# UDEMY_Sheet.net
KiCad netlist of a schematic drawn in Altium Designer
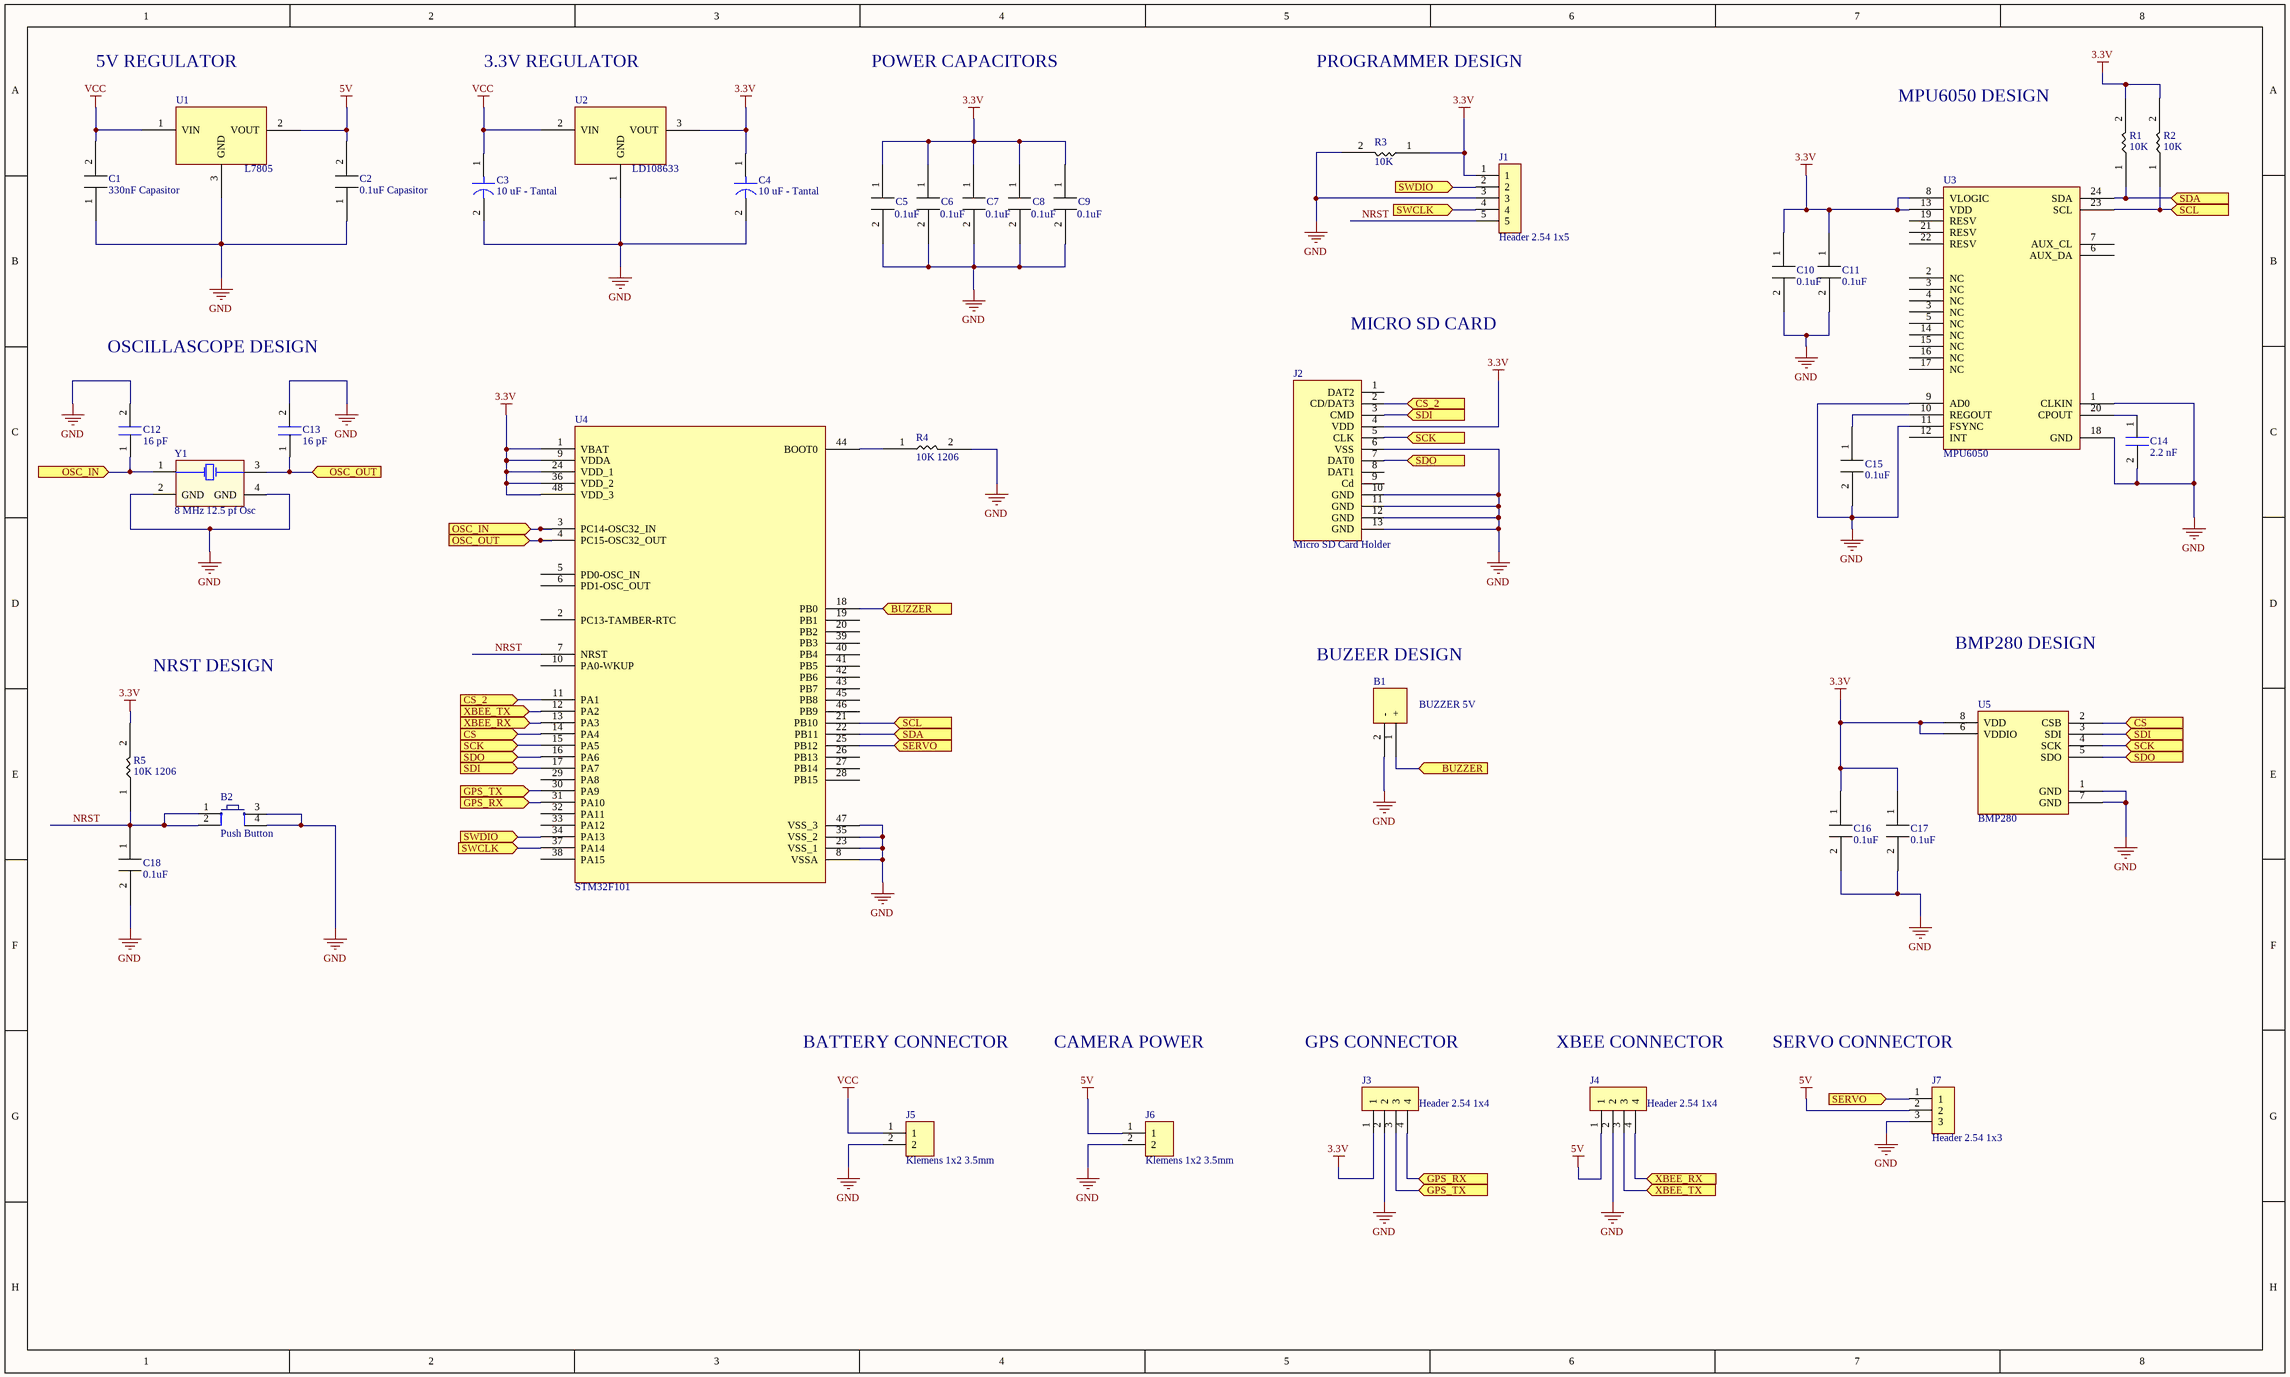
[diagram p0: UDEMY_Sheet.SchDoc]

(export (version "E")
  (design (tool "Eeschema 10.0.6"))
  (components
    (comp (ref "B1")
      (value "BUZZER 5V")
      (footprint "BUZZER 5V")
      (libsource (lib "UDEMY_Schlib1SchLib") (part "BUZZER 5V"))
    )
    (comp (ref "B2")
      (value "Push Button")
      (footprint "PUSB BUTTON-SMD")
      (description "Smd Push Button")
      (libsource (lib "UDEMY_Schlib1SchLib") (part "Push Button"))
    )
    (comp (ref "C1")
      (value "330nF Capasitor")
      (footprint "CAP 1206")
      (libsource (lib "UDEMY_Schlib1SchLib") (part "330nF Capasitor"))
    )
    (comp (ref "C2")
      (value "0.1uF Capasitor")
      (footprint "CAP 1206")
      (libsource (lib "UDEMY_Schlib1SchLib") (part "0.1uF Capasitor"))
    )
    (comp (ref "C3")
      (value "10 uF - Tantal")
      (footprint "C1206- TANTAL")
      (libsource (lib "UDEMY_Schlib1SchLib") (part "10 uF - Tantal"))
    )
    (comp (ref "C4")
      (value "10 uF - Tantal")
      (footprint "C1206- TANTAL")
      (libsource (lib "UDEMY_Schlib1SchLib") (part "10 uF - Tantal"))
    )
    (comp (ref "C5")
      (value "0.1uF")
      (footprint "CAP 1206")
      (description "0.1uF Capasitor")
      (libsource (lib "UDEMY_Schlib1SchLib") (part "0.1uF Capasitor"))
    )
    (comp (ref "C6")
      (value "0.1uF")
      (footprint "CAP 1206")
      (description "0.1uF Capasitor")
      (libsource (lib "UDEMY_Schlib1SchLib") (part "0.1uF Capasitor"))
    )
    (comp (ref "C7")
      (value "0.1uF")
      (footprint "CAP 1206")
      (description "0.1uF Capasitor")
      (libsource (lib "UDEMY_Schlib1SchLib") (part "0.1uF Capasitor"))
    )
    (comp (ref "C8")
      (value "0.1uF")
      (footprint "CAP 1206")
      (description "0.1uF Capasitor")
      (libsource (lib "UDEMY_Schlib1SchLib") (part "0.1uF Capasitor"))
    )
    (comp (ref "C9")
      (value "0.1uF")
      (footprint "CAP 1206")
      (description "0.1uF Capasitor")
      (libsource (lib "UDEMY_Schlib1SchLib") (part "0.1uF Capasitor"))
    )
    (comp (ref "C10")
      (value "0.1uF")
      (footprint "CAP 1206")
      (description "0.1uF Capasitor")
      (libsource (lib "UDEMY_Schlib1SchLib") (part "0.1uF Capasitor"))
    )
    (comp (ref "C11")
      (value "0.1uF")
      (footprint "CAP 1206")
      (description "0.1uF Capasitor")
      (libsource (lib "UDEMY_Schlib1SchLib") (part "0.1uF Capasitor"))
    )
    (comp (ref "C12")
      (value "16 pF")
      (footprint "CAP 1206")
      (libsource (lib "UDEMY_Schlib1SchLib") (part "16 pF"))
    )
    (comp (ref "C13")
      (value "16 pF")
      (footprint "CAP 1206")
      (libsource (lib "UDEMY_Schlib1SchLib") (part "16 pF"))
    )
    (comp (ref "C14")
      (value "2.2 nF")
      (footprint "CAP 1206")
      (description "2.2 nF c1206")
      (libsource (lib "UDEMY_Schlib1SchLib") (part "2.2 nF c1206"))
    )
    (comp (ref "C15")
      (value "0.1uF")
      (footprint "CAP 1206")
      (description "0.1uF Capasitor")
      (libsource (lib "UDEMY_Schlib1SchLib") (part "0.1uF Capasitor"))
    )
    (comp (ref "C16")
      (value "0.1uF")
      (footprint "CAP 1206")
      (description "0.1uF Capasitor")
      (libsource (lib "UDEMY_Schlib1SchLib") (part "0.1uF Capasitor"))
    )
    (comp (ref "C17")
      (value "0.1uF")
      (footprint "CAP 1206")
      (description "0.1uF Capasitor")
      (libsource (lib "UDEMY_Schlib1SchLib") (part "0.1uF Capasitor"))
    )
    (comp (ref "C18")
      (value "0.1uF")
      (footprint "CAP 1206")
      (description "0.1uF Capasitor")
      (libsource (lib "UDEMY_Schlib1SchLib") (part "0.1uF Capasitor"))
    )
    (comp (ref "J1")
      (value "Header 2.54 1x5")
      (footprint "Header 2.54 1x5")
      (libsource (lib "UDEMY_Schlib1SchLib") (part "Header 2.54 1x5"))
    )
    (comp (ref "J2")
      (value "Micro SD Card Holder")
      (footprint "Micro SD Card Holder")
      (libsource (lib "UDEMY_Schlib1SchLib") (part "Micro SD Card Holder"))
    )
    (comp (ref "J3")
      (value "Header 2.54 1x4")
      (footprint "Header 2.54 1x4")
      (libsource (lib "UDEMY_Schlib1SchLib") (part "Header 2.54 1x4"))
    )
    (comp (ref "J4")
      (value "Header 2.54 1x4")
      (footprint "Header 2.54 1x4")
      (libsource (lib "UDEMY_Schlib1SchLib") (part "Header 2.54 1x4"))
    )
    (comp (ref "J5")
      (value "Klemens 1x2 3.5mm")
      (footprint "Klemens 1x2 - 3.5mm")
      (libsource (lib "UDEMY_Schlib1SchLib") (part "Klemens 1x2 3.5mm"))
    )
    (comp (ref "J6")
      (value "Klemens 1x2 3.5mm")
      (footprint "Klemens 1x2 - 3.5mm")
      (libsource (lib "UDEMY_Schlib1SchLib") (part "Klemens 1x2 3.5mm"))
    )
    (comp (ref "J7")
      (value "Header 2.54 1x3")
      (footprint "Header 2.54 1x3")
      (libsource (lib "UDEMY_Schlib1SchLib") (part "Header 2.54 1x3"))
    )
    (comp (ref "R1")
      (value "10K")
      (footprint "1206 RES")
      (description "10K 1206")
      (libsource (lib "UDEMY_Schlib1SchLib") (part "10K 1206"))
    )
    (comp (ref "R2")
      (value "10K")
      (footprint "1206 RES")
      (description "10K 1206")
      (libsource (lib "UDEMY_Schlib1SchLib") (part "10K 1206"))
    )
    (comp (ref "R3")
      (value "10K")
      (footprint "1206 RES")
      (description "10K 1206")
      (libsource (lib "UDEMY_Schlib1SchLib") (part "10K 1206"))
    )
    (comp (ref "R4")
      (value "10K 1206")
      (footprint "1206 RES")
      (libsource (lib "UDEMY_Schlib1SchLib") (part "10K 1206"))
    )
    (comp (ref "R5")
      (value "10K 1206")
      (footprint "1206 RES")
      (libsource (lib "UDEMY_Schlib1SchLib") (part "10K 1206"))
    )
    (comp (ref "U1")
      (value "L7805")
      (footprint "DPAK228P972X230-3N")
      (description "L7805 5V REGULATOR DPAK")
      (libsource (lib "UDEMY_Schlib1SchLib") (part "L7805"))
    )
    (comp (ref "U2")
      (value "LD108633")
      (footprint "DPAK228P972X230-3N")
      (description "LD108633 3.3V REGULATOR DPAK")
      (libsource (lib "UDEMY_Schlib1SchLib") (part "LD108633"))
    )
    (comp (ref "U3")
      (value "MPU6050")
      (footprint "QFN50P400X400X90_HS-25N")
      (description "MPU6050 GYRO")
      (libsource (lib "UDEMY_Schlib1SchLib") (part "MPU6050"))
    )
    (comp (ref "U4")
      (value "STM32F101")
      (footprint "LQFP48-STM")
      (description "STM32F101 48 pinli mikrodenetleyicisi")
      (libsource (lib "UDEMY_Schlib1SchLib") (part "STM32F101"))
    )
    (comp (ref "U5")
      (value "BMP280")
      (footprint "BMP280")
      (description "BMP280 SENSOR")
      (libsource (lib "UDEMY_Schlib1SchLib") (part "BMP280"))
    )
    (comp (ref "Y1")
      (value "8 MHz 12.5 pf Osc")
      (footprint "8 MHZ Osc.")
      (libsource (lib "UDEMY_Schlib1SchLib") (part "8 MHz 12.5 pf Osc"))
    )
  )
  (nets
    (net (code "1") (name "/BUZZER") (class "Default")
      (node (ref "B1") (pin "1") (pinfunction "+_1") (pintype "passive"))
      (node (ref "U4") (pin "18") (pinfunction "PB0_18") (pintype "passive"))
    )
    (net (code "2") (name "/CS") (class "Default")
      (node (ref "U4") (pin "14") (pinfunction "PA4_14") (pintype "passive"))
      (node (ref "U5") (pin "2") (pinfunction "CSB_2") (pintype "passive"))
    )
    (net (code "3") (name "/CS_2") (class "Default")
      (node (ref "J2") (pin "2") (pinfunction "CD/DAT3_2") (pintype "passive"))
      (node (ref "U4") (pin "11") (pinfunction "PA1_11") (pintype "passive"))
    )
    (net (code "4") (name "/GPS_RX") (class "Default")
      (node (ref "J3") (pin "4") (pinfunction "4_4") (pintype "passive"))
      (node (ref "U4") (pin "31") (pinfunction "PA10_31") (pintype "passive"))
    )
    (net (code "5") (name "/GPS_TX") (class "Default")
      (node (ref "J3") (pin "3") (pinfunction "3_3") (pintype "passive"))
      (node (ref "U4") (pin "30") (pinfunction "PA9_30") (pintype "passive"))
    )
    (net (code "6") (name "/NRST") (class "Default")
      (node (ref "B2") (pin "1") (pinfunction "1_1") (pintype "passive"))
      (node (ref "B2") (pin "2") (pinfunction "2_2") (pintype "passive"))
      (node (ref "C18") (pin "1") (pinfunction "1_1") (pintype "passive"))
      (node (ref "J1") (pin "5") (pinfunction "5_5") (pintype "passive"))
      (node (ref "R5") (pin "1") (pinfunction "1_1") (pintype "passive"))
      (node (ref "U4") (pin "7") (pinfunction "NRST_7") (pintype "passive"))
    )
    (net (code "7") (name "/OSC_IN") (class "Default")
      (node (ref "C12") (pin "1") (pinfunction "1_1") (pintype "passive"))
      (node (ref "U4") (pin "3") (pinfunction "PC14-OSC32_IN_3") (pintype "passive"))
      (node (ref "Y1") (pin "1") (pintype "power_in"))
    )
    (net (code "8") (name "/OSC_OUT") (class "Default")
      (node (ref "C13") (pin "1") (pinfunction "1_1") (pintype "passive"))
      (node (ref "U4") (pin "4") (pinfunction "PC15-OSC32_OUT_4") (pintype "passive"))
      (node (ref "Y1") (pin "3") (pintype "passive"))
    )
    (net (code "9") (name "/SCK") (class "Default")
      (node (ref "J2") (pin "5") (pinfunction "CLK_5") (pintype "passive"))
      (node (ref "U4") (pin "15") (pinfunction "PA5_15") (pintype "passive"))
      (node (ref "U5") (pin "4") (pinfunction "SCK_4") (pintype "passive"))
    )
    (net (code "10") (name "/SCL") (class "Default")
      (node (ref "R2") (pin "1") (pinfunction "1_1") (pintype "passive"))
      (node (ref "U3") (pin "23") (pinfunction "SCL_23") (pintype "passive"))
      (node (ref "U4") (pin "21") (pinfunction "PB10_21") (pintype "passive"))
    )
    (net (code "11") (name "/SDA") (class "Default")
      (node (ref "R1") (pin "1") (pinfunction "1_1") (pintype "passive"))
      (node (ref "U3") (pin "24") (pinfunction "SDA_24") (pintype "passive"))
      (node (ref "U4") (pin "22") (pinfunction "PB11_22") (pintype "passive"))
    )
    (net (code "12") (name "/SDI") (class "Default")
      (node (ref "J2") (pin "3") (pinfunction "CMD_3") (pintype "passive"))
      (node (ref "U4") (pin "17") (pinfunction "PA7_17") (pintype "passive"))
      (node (ref "U5") (pin "3") (pinfunction "SDI_3") (pintype "passive"))
    )
    (net (code "13") (name "/SDO") (class "Default")
      (node (ref "J2") (pin "7") (pinfunction "DAT0_7") (pintype "passive"))
      (node (ref "U4") (pin "16") (pinfunction "PA6_16") (pintype "passive"))
      (node (ref "U5") (pin "5") (pinfunction "SDO_5") (pintype "passive"))
    )
    (net (code "14") (name "/SERVO") (class "Default")
      (node (ref "J7") (pin "1") (pinfunction "1_1") (pintype "passive"))
      (node (ref "U4") (pin "25") (pinfunction "PB12_25") (pintype "passive"))
    )
    (net (code "15") (name "/SWCLK") (class "Default")
      (node (ref "J1") (pin "4") (pinfunction "4_4") (pintype "passive"))
      (node (ref "U4") (pin "37") (pinfunction "PA14_37") (pintype "passive"))
    )
    (net (code "16") (name "/SWDIO") (class "Default")
      (node (ref "J1") (pin "2") (pinfunction "2_2") (pintype "passive"))
      (node (ref "U4") (pin "34") (pinfunction "PA13_34") (pintype "passive"))
    )
    (net (code "17") (name "/XBEE_RX") (class "Default")
      (node (ref "J4") (pin "4") (pinfunction "4_4") (pintype "passive"))
      (node (ref "U4") (pin "13") (pinfunction "PA3_13") (pintype "passive"))
    )
    (net (code "18") (name "/XBEE_TX") (class "Default")
      (node (ref "J4") (pin "3") (pinfunction "3_3") (pintype "passive"))
      (node (ref "U4") (pin "12") (pinfunction "PA2_12") (pintype "passive"))
    )
    (net (code "19") (name "3.3V") (class "Default")
      (node (ref "C10") (pin "1") (pinfunction "1_1") (pintype "passive"))
      (node (ref "C11") (pin "1") (pinfunction "1_1") (pintype "passive"))
      (node (ref "C16") (pin "1") (pinfunction "1_1") (pintype "passive"))
      (node (ref "C17") (pin "1") (pinfunction "1_1") (pintype "passive"))
      (node (ref "C4") (pin "1") (pinfunction "1_1") (pintype "passive"))
      (node (ref "C5") (pin "1") (pinfunction "1_1") (pintype "passive"))
      (node (ref "C6") (pin "1") (pinfunction "1_1") (pintype "passive"))
      (node (ref "C7") (pin "1") (pinfunction "1_1") (pintype "passive"))
      (node (ref "C8") (pin "1") (pinfunction "1_1") (pintype "passive"))
      (node (ref "C9") (pin "1") (pinfunction "1_1") (pintype "passive"))
      (node (ref "J1") (pin "1") (pinfunction "1_1") (pintype "passive"))
      (node (ref "J2") (pin "4") (pinfunction "VDD_4") (pintype "passive"))
      (node (ref "J3") (pin "1") (pinfunction "1_1") (pintype "passive"))
      (node (ref "R1") (pin "2") (pinfunction "2_2") (pintype "passive"))
      (node (ref "R2") (pin "2") (pinfunction "2_2") (pintype "passive"))
      (node (ref "R3") (pin "1") (pinfunction "1_1") (pintype "passive"))
      (node (ref "R5") (pin "2") (pinfunction "2_2") (pintype "passive"))
      (node (ref "U2") (pin "3") (pinfunction "VOUT_3") (pintype "passive"))
      (node (ref "U3") (pin "13") (pinfunction "VDD_13") (pintype "passive"))
      (node (ref "U3") (pin "8") (pinfunction "VLOGIC_8") (pintype "passive"))
      (node (ref "U4") (pin "1") (pinfunction "VBAT_1") (pintype "passive"))
      (node (ref "U4") (pin "24") (pinfunction "VDD_1_24") (pintype "passive"))
      (node (ref "U4") (pin "36") (pinfunction "VDD_2_36") (pintype "passive"))
      (node (ref "U4") (pin "48") (pinfunction "VDD_3_48") (pintype "passive"))
      (node (ref "U4") (pin "9") (pinfunction "VDDA_9") (pintype "passive"))
      (node (ref "U5") (pin "6") (pinfunction "VDDIO_6") (pintype "passive"))
      (node (ref "U5") (pin "8") (pinfunction "VDD_8") (pintype "passive"))
    )
    (net (code "20") (name "5V") (class "Default")
      (node (ref "C2") (pin "2") (pinfunction "2_2") (pintype "passive"))
      (node (ref "J4") (pin "1") (pinfunction "1_1") (pintype "passive"))
      (node (ref "J6") (pin "1") (pinfunction "1_1") (pintype "passive"))
      (node (ref "J7") (pin "2") (pinfunction "2_2") (pintype "passive"))
      (node (ref "U1") (pin "2") (pinfunction "VOUT_2") (pintype "passive"))
    )
    (net (code "21") (name "GND") (class "Default")
      (node (ref "B1") (pin "2") (pinfunction "-_2") (pintype "passive"))
      (node (ref "B2") (pin "3") (pinfunction "3_3") (pintype "passive"))
      (node (ref "B2") (pin "4") (pinfunction "4_4") (pintype "passive"))
      (node (ref "C1") (pin "1") (pinfunction "1_1") (pintype "passive"))
      (node (ref "C10") (pin "2") (pinfunction "2_2") (pintype "passive"))
      (node (ref "C11") (pin "2") (pinfunction "2_2") (pintype "passive"))
      (node (ref "C12") (pin "2") (pinfunction "2_2") (pintype "passive"))
      (node (ref "C13") (pin "2") (pinfunction "2_2") (pintype "passive"))
      (node (ref "C14") (pin "2") (pinfunction "2_2") (pintype "passive"))
      (node (ref "C15") (pin "2") (pinfunction "2_2") (pintype "passive"))
      (node (ref "C16") (pin "2") (pinfunction "2_2") (pintype "passive"))
      (node (ref "C17") (pin "2") (pinfunction "2_2") (pintype "passive"))
      (node (ref "C18") (pin "2") (pinfunction "2_2") (pintype "passive"))
      (node (ref "C2") (pin "1") (pinfunction "1_1") (pintype "passive"))
      (node (ref "C3") (pin "2") (pinfunction "2_2") (pintype "passive"))
      (node (ref "C4") (pin "2") (pinfunction "2_2") (pintype "passive"))
      (node (ref "C5") (pin "2") (pinfunction "2_2") (pintype "passive"))
      (node (ref "C6") (pin "2") (pinfunction "2_2") (pintype "passive"))
      (node (ref "C7") (pin "2") (pinfunction "2_2") (pintype "passive"))
      (node (ref "C8") (pin "2") (pinfunction "2_2") (pintype "passive"))
      (node (ref "C9") (pin "2") (pinfunction "2_2") (pintype "passive"))
      (node (ref "J1") (pin "3") (pinfunction "3_3") (pintype "passive"))
      (node (ref "J2") (pin "10") (pinfunction "GND_10") (pintype "passive"))
      (node (ref "J2") (pin "11") (pinfunction "GND_11") (pintype "passive"))
      (node (ref "J2") (pin "12") (pinfunction "GND_12") (pintype "passive"))
      (node (ref "J2") (pin "13") (pinfunction "GND_13") (pintype "passive"))
      (node (ref "J2") (pin "6") (pinfunction "VSS_6") (pintype "passive"))
      (node (ref "J3") (pin "2") (pinfunction "2_2") (pintype "passive"))
      (node (ref "J4") (pin "2") (pinfunction "2_2") (pintype "passive"))
      (node (ref "J5") (pin "2") (pinfunction "2_2") (pintype "passive"))
      (node (ref "J6") (pin "2") (pinfunction "2_2") (pintype "passive"))
      (node (ref "J7") (pin "3") (pinfunction "3_3") (pintype "passive"))
      (node (ref "R3") (pin "2") (pinfunction "2_2") (pintype "passive"))
      (node (ref "R4") (pin "2") (pinfunction "2_2") (pintype "passive"))
      (node (ref "U1") (pin "3") (pinfunction "GND_3") (pintype "passive"))
      (node (ref "U2") (pin "1") (pinfunction "GND_1") (pintype "passive"))
      (node (ref "U3") (pin "1") (pinfunction "CLKIN_1") (pintype "passive"))
      (node (ref "U3") (pin "11") (pinfunction "FSYNC_11") (pintype "passive"))
      (node (ref "U3") (pin "18") (pinfunction "GND_18") (pintype "passive"))
      (node (ref "U3") (pin "9") (pinfunction "AD0_9") (pintype "passive"))
      (node (ref "U4") (pin "23") (pinfunction "VSS_1_23") (pintype "passive"))
      (node (ref "U4") (pin "35") (pinfunction "VSS_2_35") (pintype "passive"))
      (node (ref "U4") (pin "47") (pinfunction "VSS_3_47") (pintype "passive"))
      (node (ref "U4") (pin "8") (pinfunction "VSSA_8") (pintype "passive"))
      (node (ref "U5") (pin "1") (pinfunction "GND_1") (pintype "passive"))
      (node (ref "U5") (pin "7") (pinfunction "GND_7") (pintype "passive"))
      (node (ref "Y1") (pin "2") (pinfunction "GND_2") (pintype "power_in"))
      (node (ref "Y1") (pin "4") (pinfunction "GND_4") (pintype "passive"))
    )
    (net (code "22") (name "Net-(U3-CPOUT)") (class "Default")
      (node (ref "C14") (pin "1") (pinfunction "1_1") (pintype "passive"))
      (node (ref "U3") (pin "20") (pinfunction "CPOUT_20") (pintype "passive"))
    )
    (net (code "23") (name "Net-(U3-REGOUT)") (class "Default")
      (node (ref "C15") (pin "1") (pinfunction "1_1") (pintype "passive"))
      (node (ref "U3") (pin "10") (pinfunction "REGOUT_10") (pintype "passive"))
    )
    (net (code "24") (name "Net-(U4-BOOT0)") (class "Default")
      (node (ref "R4") (pin "1") (pinfunction "1_1") (pintype "passive"))
      (node (ref "U4") (pin "44") (pinfunction "BOOT0_44") (pintype "passive"))
    )
    (net (code "25") (name "VCC") (class "Default")
      (node (ref "C1") (pin "2") (pinfunction "2_2") (pintype "passive"))
      (node (ref "C3") (pin "1") (pinfunction "1_1") (pintype "passive"))
      (node (ref "J5") (pin "1") (pinfunction "1_1") (pintype "passive"))
      (node (ref "U1") (pin "1") (pinfunction "VIN_1") (pintype "passive"))
      (node (ref "U2") (pin "2") (pinfunction "VIN_2") (pintype "passive"))
    )
    (net (code "26") (name "unconnected-(J2-Cd-Pad9)") (class "Default")
      (node (ref "J2") (pin "9") (pinfunction "Cd_9") (pintype "passive"))
    )
    (net (code "27") (name "unconnected-(J2-DAT1-Pad8)") (class "Default")
      (node (ref "J2") (pin "8") (pinfunction "DAT1_8") (pintype "passive"))
    )
    (net (code "28") (name "unconnected-(J2-DAT2-Pad1)") (class "Default")
      (node (ref "J2") (pin "1") (pinfunction "DAT2_1") (pintype "passive"))
    )
    (net (code "29") (name "unconnected-(U3-AUX_CL-Pad7)") (class "Default")
      (node (ref "U3") (pin "7") (pinfunction "AUX_CL_7") (pintype "passive"))
    )
    (net (code "30") (name "unconnected-(U3-AUX_DA-Pad6)") (class "Default")
      (node (ref "U3") (pin "6") (pinfunction "AUX_DA_6") (pintype "passive"))
    )
    (net (code "31") (name "unconnected-(U3-INT-Pad12)") (class "Default")
      (node (ref "U3") (pin "12") (pinfunction "INT_12") (pintype "passive"))
    )
    (net (code "32") (name "unconnected-(U3-NC-Pad2)") (class "Default")
      (node (ref "U3") (pin "2") (pinfunction "NC_2") (pintype "passive"))
    )
    (net (code "33") (name "unconnected-(U3-NC-Pad3)") (class "Default")
      (node (ref "U3") (pin "3") (pinfunction "NC_3") (pintype "passive"))
    )
    (net (code "34") (name "unconnected-(U3-NC-Pad3)_1") (class "Default")
      (node (ref "U3") (pin "3") (pinfunction "NC_3") (pintype "passive"))
    )
    (net (code "35") (name "unconnected-(U3-NC-Pad4)") (class "Default")
      (node (ref "U3") (pin "4") (pinfunction "NC_4") (pintype "passive"))
    )
    (net (code "36") (name "unconnected-(U3-NC-Pad5)") (class "Default")
      (node (ref "U3") (pin "5") (pinfunction "NC_5") (pintype "passive"))
    )
    (net (code "37") (name "unconnected-(U3-NC-Pad14)") (class "Default")
      (node (ref "U3") (pin "14") (pinfunction "NC_14") (pintype "passive"))
    )
    (net (code "38") (name "unconnected-(U3-NC-Pad15)") (class "Default")
      (node (ref "U3") (pin "15") (pinfunction "NC_15") (pintype "passive"))
    )
    (net (code "39") (name "unconnected-(U3-NC-Pad16)") (class "Default")
      (node (ref "U3") (pin "16") (pinfunction "NC_16") (pintype "passive"))
    )
    (net (code "40") (name "unconnected-(U3-NC-Pad17)") (class "Default")
      (node (ref "U3") (pin "17") (pinfunction "NC_17") (pintype "passive"))
    )
    (net (code "41") (name "unconnected-(U3-RESV-Pad19)") (class "Default")
      (node (ref "U3") (pin "19") (pinfunction "RESV_19") (pintype "passive"))
    )
    (net (code "42") (name "unconnected-(U3-RESV-Pad21)") (class "Default")
      (node (ref "U3") (pin "21") (pinfunction "RESV_21") (pintype "passive"))
    )
    (net (code "43") (name "unconnected-(U3-RESV-Pad22)") (class "Default")
      (node (ref "U3") (pin "22") (pinfunction "RESV_22") (pintype "passive"))
    )
    (net (code "44") (name "unconnected-(U4-PA0-WKUP-Pad10)") (class "Default")
      (node (ref "U4") (pin "10") (pinfunction "PA0-WKUP_10") (pintype "passive"))
    )
    (net (code "45") (name "unconnected-(U4-PA8-Pad29)") (class "Default")
      (node (ref "U4") (pin "29") (pinfunction "PA8_29") (pintype "passive"))
    )
    (net (code "46") (name "unconnected-(U4-PA11-Pad32)") (class "Default")
      (node (ref "U4") (pin "32") (pinfunction "PA11_32") (pintype "passive"))
    )
    (net (code "47") (name "unconnected-(U4-PA12-Pad33)") (class "Default")
      (node (ref "U4") (pin "33") (pinfunction "PA12_33") (pintype "passive"))
    )
    (net (code "48") (name "unconnected-(U4-PA15-Pad38)") (class "Default")
      (node (ref "U4") (pin "38") (pinfunction "PA15_38") (pintype "passive"))
    )
    (net (code "49") (name "unconnected-(U4-PB1-Pad19)") (class "Default")
      (node (ref "U4") (pin "19") (pinfunction "PB1_19") (pintype "passive"))
    )
    (net (code "50") (name "unconnected-(U4-PB2-Pad20)") (class "Default")
      (node (ref "U4") (pin "20") (pinfunction "PB2_20") (pintype "passive"))
    )
    (net (code "51") (name "unconnected-(U4-PB3-Pad39)") (class "Default")
      (node (ref "U4") (pin "39") (pinfunction "PB3_39") (pintype "passive"))
    )
    (net (code "52") (name "unconnected-(U4-PB4-Pad40)") (class "Default")
      (node (ref "U4") (pin "40") (pinfunction "PB4_40") (pintype "passive"))
    )
    (net (code "53") (name "unconnected-(U4-PB5-Pad41)") (class "Default")
      (node (ref "U4") (pin "41") (pinfunction "PB5_41") (pintype "passive"))
    )
    (net (code "54") (name "unconnected-(U4-PB6-Pad42)") (class "Default")
      (node (ref "U4") (pin "42") (pinfunction "PB6_42") (pintype "passive"))
    )
    (net (code "55") (name "unconnected-(U4-PB7-Pad43)") (class "Default")
      (node (ref "U4") (pin "43") (pinfunction "PB7_43") (pintype "passive"))
    )
    (net (code "56") (name "unconnected-(U4-PB8-Pad45)") (class "Default")
      (node (ref "U4") (pin "45") (pinfunction "PB8_45") (pintype "passive"))
    )
    (net (code "57") (name "unconnected-(U4-PB9-Pad46)") (class "Default")
      (node (ref "U4") (pin "46") (pinfunction "PB9_46") (pintype "passive"))
    )
    (net (code "58") (name "unconnected-(U4-PB13-Pad26)") (class "Default")
      (node (ref "U4") (pin "26") (pinfunction "PB13_26") (pintype "passive"))
    )
    (net (code "59") (name "unconnected-(U4-PB14-Pad27)") (class "Default")
      (node (ref "U4") (pin "27") (pinfunction "PB14_27") (pintype "passive"))
    )
    (net (code "60") (name "unconnected-(U4-PB15-Pad28)") (class "Default")
      (node (ref "U4") (pin "28") (pinfunction "PB15_28") (pintype "passive"))
    )
    (net (code "61") (name "unconnected-(U4-PC13-TAMBER-RTC-Pad2)") (class "Default")
      (node (ref "U4") (pin "2") (pinfunction "PC13-TAMBER-RTC_2") (pintype "passive"))
    )
    (net (code "62") (name "unconnected-(U4-PD0-OSC_IN-Pad5)") (class "Default")
      (node (ref "U4") (pin "5") (pinfunction "PD0-OSC_IN_5") (pintype "passive"))
    )
    (net (code "63") (name "unconnected-(U4-PD1-OSC_OUT-Pad6)") (class "Default")
      (node (ref "U4") (pin "6") (pinfunction "PD1-OSC_OUT_6") (pintype "passive"))
    )
  )
)
